# Voltmetr_MEZ.net
KiCad netlist of a schematic drawn in Altium Designer
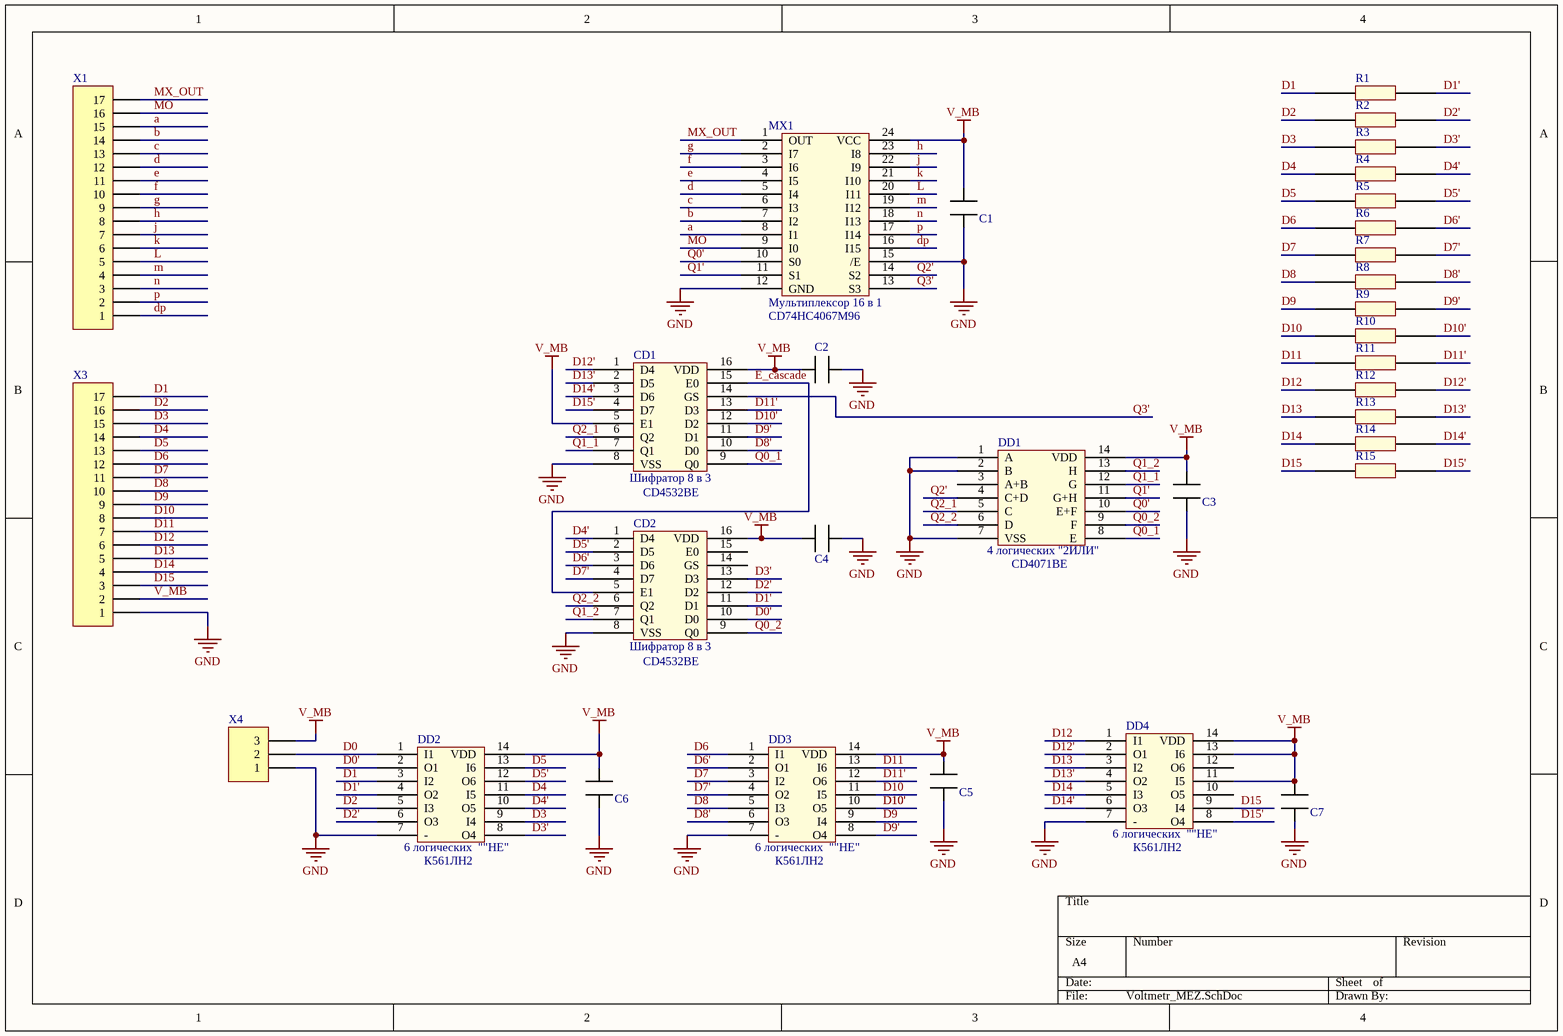
[diagram p0: Voltmetr_MEZ.SchDoc]

(export (version "E")
  (design (tool "Eeschema 10.0.6"))
  (components
    (comp (ref "C1")
      (value "CAP_SMALL")
      (footprint "CAP_SMALL")
      (libsource (lib "vpl_Schlib") (part "CAP_SMALL"))
    )
    (comp (ref "C2")
      (value "CAP_SMALL")
      (footprint "CAP_SMALL")
      (libsource (lib "vpl_Schlib") (part "CAP_SMALL"))
    )
    (comp (ref "C3")
      (value "CAP_SMALL")
      (footprint "CAP_SMALL")
      (libsource (lib "vpl_Schlib") (part "CAP_SMALL"))
    )
    (comp (ref "C4")
      (value "CAP_SMALL")
      (footprint "CAP_SMALL")
      (libsource (lib "vpl_Schlib") (part "CAP_SMALL"))
    )
    (comp (ref "C5")
      (value "CAP_SMALL")
      (footprint "CAP_SMALL")
      (libsource (lib "vpl_Schlib") (part "CAP_SMALL"))
    )
    (comp (ref "C6")
      (value "CAP_SMALL")
      (footprint "CAP_SMALL")
      (libsource (lib "vpl_Schlib") (part "CAP_SMALL"))
    )
    (comp (ref "C7")
      (value "CAP_SMALL")
      (footprint "CAP_SMALL")
      (libsource (lib "vpl_Schlib") (part "CAP_SMALL"))
    )
    (comp (ref "CD1")
      (value "CD4532BE")
      (footprint "DIP16_PANNEL")
      (description "Шифратор приоритетный 8 - 3 [DIP-16]")
      (libsource (lib "msp_SchLib") (part "CD4532BE"))
    )
    (comp (ref "CD2")
      (value "CD4532BE")
      (footprint "DIP16_PANNEL")
      (description "Шифратор приоритетный 8 - 3 [DIP-16]")
      (libsource (lib "msp_SchLib") (part "CD4532BE"))
    )
    (comp (ref "DD1")
      (value "CD4071BE")
      (footprint "Dip14_pannel")
      (description "Четыре логических элемента \"2ИЛИ\", [DIP-14]")
      (libsource (lib "msp_SchLib") (part "CD4071BE"))
    )
    (comp (ref "DD2")
      (value "К561ЛН2")
      (footprint "Dip14_pannel")
      (description "Шесть логических элементов \"HЕ\" (DIP-14)")
      (libsource (lib "msp_SchLib") (part "К561ЛН2"))
    )
    (comp (ref "DD3")
      (value "К561ЛН2")
      (footprint "Dip14_pannel")
      (description "Шесть логических элементов \"HЕ\" (DIP-14)")
      (libsource (lib "msp_SchLib") (part "К561ЛН2"))
    )
    (comp (ref "DD4")
      (value "К561ЛН2")
      (footprint "Dip14_pannel")
      (description "Шесть логических элементов \"HЕ\" (DIP-14)")
      (libsource (lib "msp_SchLib") (part "К561ЛН2"))
    )
    (comp (ref "MX1")
      (value "CD74HC4067M96")
      (footprint "SOIC-24")
      (description "16-и канальный аналоговый мультиплексор/ демультиплексор, [SO-24]")
      (libsource (lib "msp_SchLib") (part "CD74HC4067M96"))
    )
    (comp (ref "R1") (value "resistor") (footprint "RES 0805") (libsource (lib "msp_SchLib") (part "RES")))
    (comp (ref "R2") (value "resistor") (footprint "RES 0805") (libsource (lib "msp_SchLib") (part "RES")))
    (comp (ref "R3") (value "resistor") (footprint "RES 0805") (libsource (lib "msp_SchLib") (part "RES")))
    (comp (ref "R4") (value "resistor") (footprint "RES 0805") (libsource (lib "msp_SchLib") (part "RES")))
    (comp (ref "R5") (value "resistor") (footprint "RES 0805") (libsource (lib "msp_SchLib") (part "RES")))
    (comp (ref "R6") (value "resistor") (footprint "RES 0805") (libsource (lib "msp_SchLib") (part "RES")))
    (comp (ref "R7") (value "resistor") (footprint "RES 0805") (libsource (lib "msp_SchLib") (part "RES")))
    (comp (ref "R8") (value "resistor") (footprint "RES 0805") (libsource (lib "msp_SchLib") (part "RES")))
    (comp (ref "R9") (value "resistor") (footprint "RES 0805") (libsource (lib "msp_SchLib") (part "RES")))
    (comp (ref "R10") (value "resistor") (footprint "RES 0805") (libsource (lib "msp_SchLib") (part "RES")))
    (comp (ref "R11") (value "resistor") (footprint "RES 0805") (libsource (lib "msp_SchLib") (part "RES")))
    (comp (ref "R12") (value "resistor") (footprint "RES 0805") (libsource (lib "msp_SchLib") (part "RES")))
    (comp (ref "R13") (value "resistor") (footprint "RES 0805") (libsource (lib "msp_SchLib") (part "RES")))
    (comp (ref "R14") (value "resistor") (footprint "RES 0805") (libsource (lib "msp_SchLib") (part "RES")))
    (comp (ref "R15") (value "resistor") (footprint "RES 0805") (libsource (lib "msp_SchLib") (part "RES")))
    (comp (ref "X1")
      (value "Header 17")
      (footprint "HDR1X17")
      (description "Header, 17-Pin")
      (fields (field (name "PUBLISHER") "Altium Limited"))
      (libsource (lib "Miscellaneous Connectors") (part "Header 17"))
    )
    (comp (ref "X3")
      (value "Header 17")
      (footprint "HDR1X17")
      (description "Header, 17-Pin")
      (fields (field (name "PUBLISHER") "Altium Limited"))
      (libsource (lib "Miscellaneous Connectors") (part "Header 17"))
    )
    (comp (ref "X4")
      (value "Header 3")
      (footprint "HDR1X3")
      (description "Header, 3-Pin")
      (fields (field (name "PUBLISHER") "Altium Limited"))
      (libsource (lib "Miscellaneous Connectors") (part "Header 3"))
    )
  )
  (nets
    (net (code "2") (name "/D0") (class "Default")
      (node (ref "DD2") (pin "1") (pinfunction "I1_1") (pintype "passive"))
      (node (ref "X4") (pin "2") (pinfunction "2_2") (pintype "passive"))
    )
    (net (code "3") (name "/D0'") (class "Default")
      (node (ref "CD2") (pin "10") (pinfunction "D0_10") (pintype "passive"))
      (node (ref "DD2") (pin "2") (pinfunction "O1_2") (pintype "passive"))
    )
    (net (code "4") (name "/D1") (class "Default")
      (node (ref "DD2") (pin "3") (pinfunction "I2_3") (pintype "passive"))
      (node (ref "R1") (pin "1") (pinfunction "1_1") (pintype "passive"))
      (node (ref "X3") (pin "17") (pinfunction "17_17") (pintype "passive"))
    )
    (net (code "5") (name "/D1'") (class "Default")
      (node (ref "CD2") (pin "11") (pinfunction "D1_11") (pintype "passive"))
      (node (ref "DD2") (pin "4") (pinfunction "O2_4") (pintype "passive"))
      (node (ref "R1") (pin "2") (pinfunction "2_2") (pintype "passive"))
    )
    (net (code "6") (name "/D2") (class "Default")
      (node (ref "DD2") (pin "5") (pinfunction "I3_5") (pintype "passive"))
      (node (ref "R2") (pin "1") (pinfunction "1_1") (pintype "passive"))
      (node (ref "X3") (pin "16") (pinfunction "16_16") (pintype "passive"))
    )
    (net (code "7") (name "/D2'") (class "Default")
      (node (ref "CD2") (pin "12") (pinfunction "D2_12") (pintype "passive"))
      (node (ref "DD2") (pin "6") (pinfunction "O3_6") (pintype "passive"))
      (node (ref "R2") (pin "2") (pinfunction "2_2") (pintype "passive"))
    )
    (net (code "8") (name "/D3") (class "Default")
      (node (ref "DD2") (pin "9") (pinfunction "I4_9") (pintype "passive"))
      (node (ref "R3") (pin "1") (pinfunction "1_1") (pintype "passive"))
      (node (ref "X3") (pin "15") (pinfunction "15_15") (pintype "passive"))
    )
    (net (code "9") (name "/D3'") (class "Default")
      (node (ref "CD2") (pin "13") (pinfunction "D3_13") (pintype "passive"))
      (node (ref "DD2") (pin "8") (pinfunction "O4_8") (pintype "passive"))
      (node (ref "R3") (pin "2") (pinfunction "2_2") (pintype "passive"))
    )
    (net (code "10") (name "/D4") (class "Default")
      (node (ref "DD2") (pin "11") (pinfunction "I5_11") (pintype "passive"))
      (node (ref "R4") (pin "1") (pinfunction "1_1") (pintype "passive"))
      (node (ref "X3") (pin "14") (pinfunction "14_14") (pintype "passive"))
    )
    (net (code "11") (name "/D4'") (class "Default")
      (node (ref "CD2") (pin "1") (pinfunction "D4_1") (pintype "passive"))
      (node (ref "DD2") (pin "10") (pinfunction "O5_10") (pintype "passive"))
      (node (ref "R4") (pin "2") (pinfunction "2_2") (pintype "passive"))
    )
    (net (code "12") (name "/D5") (class "Default")
      (node (ref "DD2") (pin "13") (pinfunction "I6_13") (pintype "passive"))
      (node (ref "R5") (pin "1") (pinfunction "1_1") (pintype "passive"))
      (node (ref "X3") (pin "13") (pinfunction "13_13") (pintype "passive"))
    )
    (net (code "13") (name "/D5'") (class "Default")
      (node (ref "CD2") (pin "2") (pinfunction "D5_2") (pintype "passive"))
      (node (ref "DD2") (pin "12") (pinfunction "O6_12") (pintype "passive"))
      (node (ref "R5") (pin "2") (pinfunction "2_2") (pintype "passive"))
    )
    (net (code "14") (name "/D6") (class "Default")
      (node (ref "DD3") (pin "1") (pinfunction "I1_1") (pintype "passive"))
      (node (ref "R6") (pin "1") (pinfunction "1_1") (pintype "passive"))
      (node (ref "X3") (pin "12") (pinfunction "12_12") (pintype "passive"))
    )
    (net (code "15") (name "/D6'") (class "Default")
      (node (ref "CD2") (pin "3") (pinfunction "D6_3") (pintype "passive"))
      (node (ref "DD3") (pin "2") (pinfunction "O1_2") (pintype "passive"))
      (node (ref "R6") (pin "2") (pinfunction "2_2") (pintype "passive"))
    )
    (net (code "16") (name "/D7") (class "Default")
      (node (ref "DD3") (pin "3") (pinfunction "I2_3") (pintype "passive"))
      (node (ref "R7") (pin "1") (pinfunction "1_1") (pintype "passive"))
      (node (ref "X3") (pin "11") (pinfunction "11_11") (pintype "passive"))
    )
    (net (code "17") (name "/D7'") (class "Default")
      (node (ref "CD2") (pin "4") (pinfunction "D7_4") (pintype "passive"))
      (node (ref "DD3") (pin "4") (pinfunction "O2_4") (pintype "passive"))
      (node (ref "R7") (pin "2") (pinfunction "2_2") (pintype "passive"))
    )
    (net (code "18") (name "/D8") (class "Default")
      (node (ref "DD3") (pin "5") (pinfunction "I3_5") (pintype "passive"))
      (node (ref "R8") (pin "1") (pinfunction "1_1") (pintype "passive"))
      (node (ref "X3") (pin "10") (pinfunction "10_10") (pintype "passive"))
    )
    (net (code "19") (name "/D8'") (class "Default")
      (node (ref "CD1") (pin "10") (pinfunction "D0_10") (pintype "passive"))
      (node (ref "DD3") (pin "6") (pinfunction "O3_6") (pintype "passive"))
      (node (ref "R8") (pin "2") (pinfunction "2_2") (pintype "passive"))
    )
    (net (code "20") (name "/D9") (class "Default")
      (node (ref "DD3") (pin "9") (pinfunction "I4_9") (pintype "passive"))
      (node (ref "R9") (pin "1") (pinfunction "1_1") (pintype "passive"))
      (node (ref "X3") (pin "9") (pinfunction "9_9") (pintype "passive"))
    )
    (net (code "21") (name "/D9'") (class "Default")
      (node (ref "CD1") (pin "11") (pinfunction "D1_11") (pintype "passive"))
      (node (ref "DD3") (pin "8") (pinfunction "O4_8") (pintype "passive"))
      (node (ref "R9") (pin "2") (pinfunction "2_2") (pintype "passive"))
    )
    (net (code "22") (name "/D10") (class "Default")
      (node (ref "DD3") (pin "11") (pinfunction "I5_11") (pintype "passive"))
      (node (ref "R10") (pin "1") (pinfunction "1_1") (pintype "passive"))
      (node (ref "X3") (pin "8") (pinfunction "8_8") (pintype "passive"))
    )
    (net (code "23") (name "/D10'") (class "Default")
      (node (ref "CD1") (pin "12") (pinfunction "D2_12") (pintype "passive"))
      (node (ref "DD3") (pin "10") (pinfunction "O5_10") (pintype "passive"))
      (node (ref "R10") (pin "2") (pinfunction "2_2") (pintype "passive"))
    )
    (net (code "24") (name "/D11") (class "Default")
      (node (ref "DD3") (pin "13") (pinfunction "I6_13") (pintype "passive"))
      (node (ref "R11") (pin "1") (pinfunction "1_1") (pintype "passive"))
      (node (ref "X3") (pin "7") (pinfunction "7_7") (pintype "passive"))
    )
    (net (code "25") (name "/D11'") (class "Default")
      (node (ref "CD1") (pin "13") (pinfunction "D3_13") (pintype "passive"))
      (node (ref "DD3") (pin "12") (pinfunction "O6_12") (pintype "passive"))
      (node (ref "R11") (pin "2") (pinfunction "2_2") (pintype "passive"))
    )
    (net (code "26") (name "/D12") (class "Default")
      (node (ref "DD4") (pin "1") (pinfunction "I1_1") (pintype "passive"))
      (node (ref "R12") (pin "1") (pinfunction "1_1") (pintype "passive"))
      (node (ref "X3") (pin "6") (pinfunction "6_6") (pintype "passive"))
    )
    (net (code "27") (name "/D12'") (class "Default")
      (node (ref "CD1") (pin "1") (pinfunction "D4_1") (pintype "passive"))
      (node (ref "DD4") (pin "2") (pinfunction "O1_2") (pintype "passive"))
      (node (ref "R12") (pin "2") (pinfunction "2_2") (pintype "passive"))
    )
    (net (code "28") (name "/D13") (class "Default")
      (node (ref "DD4") (pin "3") (pinfunction "I2_3") (pintype "passive"))
      (node (ref "R13") (pin "1") (pinfunction "1_1") (pintype "passive"))
      (node (ref "X3") (pin "5") (pinfunction "5_5") (pintype "passive"))
    )
    (net (code "29") (name "/D13'") (class "Default")
      (node (ref "CD1") (pin "2") (pinfunction "D5_2") (pintype "passive"))
      (node (ref "DD4") (pin "4") (pinfunction "O2_4") (pintype "passive"))
      (node (ref "R13") (pin "2") (pinfunction "2_2") (pintype "passive"))
    )
    (net (code "30") (name "/D14") (class "Default")
      (node (ref "DD4") (pin "5") (pinfunction "I3_5") (pintype "passive"))
      (node (ref "R14") (pin "1") (pinfunction "1_1") (pintype "passive"))
      (node (ref "X3") (pin "4") (pinfunction "4_4") (pintype "passive"))
    )
    (net (code "31") (name "/D14'") (class "Default")
      (node (ref "CD1") (pin "3") (pinfunction "D6_3") (pintype "passive"))
      (node (ref "DD4") (pin "6") (pinfunction "O3_6") (pintype "passive"))
      (node (ref "R14") (pin "2") (pinfunction "2_2") (pintype "passive"))
    )
    (net (code "32") (name "/D15") (class "Default")
      (node (ref "DD4") (pin "9") (pinfunction "I4_9") (pintype "passive"))
      (node (ref "R15") (pin "1") (pinfunction "1_1") (pintype "passive"))
      (node (ref "X3") (pin "3") (pinfunction "3_3") (pintype "passive"))
    )
    (net (code "33") (name "/D15'") (class "Default")
      (node (ref "CD1") (pin "4") (pinfunction "D7_4") (pintype "passive"))
      (node (ref "DD4") (pin "8") (pinfunction "O4_8") (pintype "passive"))
      (node (ref "R15") (pin "2") (pinfunction "2_2") (pintype "passive"))
    )
    (net (code "34") (name "/E_cascade") (class "Default")
      (node (ref "CD1") (pin "15") (pinfunction "E0_15") (pintype "passive"))
      (node (ref "CD2") (pin "5") (pinfunction "E1_5") (pintype "passive"))
    )
    (net (code "35") (name "/L") (class "Default")
      (node (ref "MX1") (pin "20") (pinfunction "I11_20") (pintype "passive"))
      (node (ref "X1") (pin "5") (pinfunction "5_5") (pintype "passive"))
    )
    (net (code "36") (name "/MX_OUT") (class "Default")
      (node (ref "MX1") (pin "1") (pinfunction "OUT_1") (pintype "passive"))
      (node (ref "X1") (pin "17") (pinfunction "17_17") (pintype "passive"))
    )
    (net (code "37") (name "/Q0'") (class "Default")
      (node (ref "DD1") (pin "10") (pinfunction "E+F_10") (pintype "passive"))
      (node (ref "MX1") (pin "10") (pinfunction "S0_10") (pintype "passive"))
    )
    (net (code "38") (name "/Q0_1") (class "Default")
      (node (ref "CD1") (pin "9") (pinfunction "Q0_9") (pintype "passive"))
      (node (ref "DD1") (pin "8") (pinfunction "E_8") (pintype "passive"))
    )
    (net (code "39") (name "/Q0_2") (class "Default")
      (node (ref "CD2") (pin "9") (pinfunction "Q0_9") (pintype "passive"))
      (node (ref "DD1") (pin "9") (pinfunction "F_9") (pintype "passive"))
    )
    (net (code "40") (name "/Q1'") (class "Default")
      (node (ref "DD1") (pin "11") (pinfunction "G+H_11") (pintype "passive"))
      (node (ref "MX1") (pin "11") (pinfunction "S1_11") (pintype "passive"))
    )
    (net (code "41") (name "/Q1_1") (class "Default")
      (node (ref "CD1") (pin "7") (pinfunction "Q1_7") (pintype "passive"))
      (node (ref "DD1") (pin "12") (pinfunction "G_12") (pintype "passive"))
    )
    (net (code "42") (name "/Q1_2") (class "Default")
      (node (ref "CD2") (pin "7") (pinfunction "Q1_7") (pintype "passive"))
      (node (ref "DD1") (pin "13") (pinfunction "H_13") (pintype "passive"))
    )
    (net (code "43") (name "/Q2'") (class "Default")
      (node (ref "DD1") (pin "4") (pinfunction "C+D_4") (pintype "passive"))
      (node (ref "MX1") (pin "14") (pinfunction "S2_14") (pintype "passive"))
    )
    (net (code "44") (name "/Q2_1") (class "Default")
      (node (ref "CD1") (pin "6") (pinfunction "Q2_6") (pintype "passive"))
      (node (ref "DD1") (pin "5") (pinfunction "C_5") (pintype "passive"))
    )
    (net (code "45") (name "/Q2_2") (class "Default")
      (node (ref "CD2") (pin "6") (pinfunction "Q2_6") (pintype "passive"))
      (node (ref "DD1") (pin "6") (pinfunction "D_6") (pintype "passive"))
    )
    (net (code "46") (name "/Q3'") (class "Default")
      (node (ref "CD1") (pin "14") (pinfunction "GS_14") (pintype "passive"))
      (node (ref "MX1") (pin "13") (pinfunction "S3_13") (pintype "passive"))
    )
    (net (code "47") (name "/a") (class "Default")
      (node (ref "MX1") (pin "8") (pinfunction "I1_8") (pintype "passive"))
      (node (ref "X1") (pin "15") (pinfunction "15_15") (pintype "passive"))
    )
    (net (code "48") (name "/b") (class "Default")
      (node (ref "MX1") (pin "7") (pinfunction "I2_7") (pintype "passive"))
      (node (ref "X1") (pin "14") (pinfunction "14_14") (pintype "passive"))
    )
    (net (code "49") (name "/c") (class "Default")
      (node (ref "MX1") (pin "6") (pinfunction "I3_6") (pintype "passive"))
      (node (ref "X1") (pin "13") (pinfunction "13_13") (pintype "passive"))
    )
    (net (code "50") (name "/d") (class "Default")
      (node (ref "MX1") (pin "5") (pinfunction "I4_5") (pintype "passive"))
      (node (ref "X1") (pin "12") (pinfunction "12_12") (pintype "passive"))
    )
    (net (code "51") (name "/dp") (class "Default")
      (node (ref "MX1") (pin "16") (pinfunction "I15_16") (pintype "passive"))
      (node (ref "X1") (pin "1") (pinfunction "1_1") (pintype "passive"))
    )
    (net (code "52") (name "/e") (class "Default")
      (node (ref "MX1") (pin "4") (pinfunction "I5_4") (pintype "passive"))
      (node (ref "X1") (pin "11") (pinfunction "11_11") (pintype "passive"))
    )
    (net (code "53") (name "/f") (class "Default")
      (node (ref "MX1") (pin "3") (pinfunction "I6_3") (pintype "passive"))
      (node (ref "X1") (pin "10") (pinfunction "10_10") (pintype "passive"))
    )
    (net (code "54") (name "/g") (class "Default")
      (node (ref "MX1") (pin "2") (pinfunction "I7_2") (pintype "passive"))
      (node (ref "X1") (pin "9") (pinfunction "9_9") (pintype "passive"))
    )
    (net (code "55") (name "/h") (class "Default")
      (node (ref "MX1") (pin "23") (pinfunction "I8_23") (pintype "passive"))
      (node (ref "X1") (pin "8") (pinfunction "8_8") (pintype "passive"))
    )
    (net (code "56") (name "/j") (class "Default")
      (node (ref "MX1") (pin "22") (pinfunction "I9_22") (pintype "passive"))
      (node (ref "X1") (pin "7") (pinfunction "7_7") (pintype "passive"))
    )
    (net (code "57") (name "/k") (class "Default")
      (node (ref "MX1") (pin "21") (pinfunction "I10_21") (pintype "passive"))
      (node (ref "X1") (pin "6") (pinfunction "6_6") (pintype "passive"))
    )
    (net (code "58") (name "/m") (class "Default")
      (node (ref "MX1") (pin "19") (pinfunction "I12_19") (pintype "passive"))
      (node (ref "X1") (pin "4") (pinfunction "4_4") (pintype "passive"))
    )
    (net (code "59") (name "/n") (class "Default")
      (node (ref "MX1") (pin "18") (pinfunction "I13_18") (pintype "passive"))
      (node (ref "X1") (pin "3") (pinfunction "3_3") (pintype "passive"))
    )
    (net (code "60") (name "/p") (class "Default")
      (node (ref "MX1") (pin "17") (pinfunction "I14_17") (pintype "passive"))
      (node (ref "X1") (pin "2") (pinfunction "2_2") (pintype "passive"))
    )
    (net (code "61") (name "/~{MO}") (class "Default")
      (node (ref "MX1") (pin "9") (pinfunction "I0_9") (pintype "passive"))
      (node (ref "X1") (pin "16") (pinfunction "16_16") (pintype "passive"))
    )
    (net (code "62") (name "GND") (class "Default")
      (node (ref "C1") (pin "1") (pinfunction "1_1") (pintype "passive"))
      (node (ref "C2") (pin "2") (pinfunction "2_2") (pintype "passive"))
      (node (ref "C3") (pin "1") (pinfunction "1_1") (pintype "passive"))
      (node (ref "C4") (pin "1") (pinfunction "1_1") (pintype "passive"))
      (node (ref "C5") (pin "1") (pinfunction "1_1") (pintype "passive"))
      (node (ref "C6") (pin "1") (pinfunction "1_1") (pintype "passive"))
      (node (ref "C7") (pin "1") (pinfunction "1_1") (pintype "passive"))
      (node (ref "CD1") (pin "8") (pinfunction "VSS_8") (pintype "passive"))
      (node (ref "CD2") (pin "8") (pinfunction "VSS_8") (pintype "passive"))
      (node (ref "DD1") (pin "1") (pinfunction "A_1") (pintype "passive"))
      (node (ref "DD1") (pin "2") (pinfunction "B_2") (pintype "passive"))
      (node (ref "DD1") (pin "7") (pinfunction "VSS_7") (pintype "passive"))
      (node (ref "DD2") (pin "7") (pinfunction "-_7") (pintype "passive"))
      (node (ref "DD3") (pin "7") (pinfunction "-_7") (pintype "passive"))
      (node (ref "DD4") (pin "7") (pinfunction "-_7") (pintype "passive"))
      (node (ref "MX1") (pin "12") (pinfunction "GND_12") (pintype "passive"))
      (node (ref "MX1") (pin "15") (pinfunction "/E_15") (pintype "passive"))
      (node (ref "X3") (pin "1") (pinfunction "1_1") (pintype "passive"))
      (node (ref "X4") (pin "1") (pinfunction "1_1") (pintype "passive"))
    )
    (net (code "63") (name "V_MB") (class "Default")
      (node (ref "C1") (pin "2") (pinfunction "2_2") (pintype "passive"))
      (node (ref "C2") (pin "1") (pinfunction "1_1") (pintype "passive"))
      (node (ref "C3") (pin "2") (pinfunction "2_2") (pintype "passive"))
      (node (ref "C4") (pin "2") (pinfunction "2_2") (pintype "passive"))
      (node (ref "C5") (pin "2") (pinfunction "2_2") (pintype "passive"))
      (node (ref "C6") (pin "2") (pinfunction "2_2") (pintype "passive"))
      (node (ref "C7") (pin "2") (pinfunction "2_2") (pintype "passive"))
      (node (ref "CD1") (pin "16") (pinfunction "VDD_16") (pintype "passive"))
      (node (ref "CD1") (pin "5") (pinfunction "E1_5") (pintype "passive"))
      (node (ref "CD2") (pin "16") (pinfunction "VDD_16") (pintype "passive"))
      (node (ref "DD1") (pin "14") (pinfunction "VDD_14") (pintype "passive"))
      (node (ref "DD2") (pin "14") (pinfunction "VDD_14") (pintype "passive"))
      (node (ref "DD3") (pin "14") (pinfunction "VDD_14") (pintype "passive"))
      (node (ref "DD4") (pin "11") (pinfunction "I5_11") (pintype "passive"))
      (node (ref "DD4") (pin "13") (pinfunction "I6_13") (pintype "passive"))
      (node (ref "DD4") (pin "14") (pinfunction "VDD_14") (pintype "passive"))
      (node (ref "MX1") (pin "24") (pinfunction "VCC_24") (pintype "passive"))
      (node (ref "X3") (pin "2") (pinfunction "2_2") (pintype "passive"))
      (node (ref "X4") (pin "3") (pinfunction "3_3") (pintype "passive"))
    )
    (net (code "64") (name "unconnected-(CD2-E0-Pad15)") (class "Default")
      (node (ref "CD2") (pin "15") (pinfunction "E0_15") (pintype "passive"))
    )
    (net (code "65") (name "unconnected-(CD2-GS-Pad14)") (class "Default")
      (node (ref "CD2") (pin "14") (pinfunction "GS_14") (pintype "passive"))
    )
    (net (code "66") (name "unconnected-(DD1-A+B-Pad3)") (class "Default")
      (node (ref "DD1") (pin "3") (pinfunction "A+B_3") (pintype "passive"))
    )
    (net (code "67") (name "unconnected-(DD4-O5-Pad10)") (class "Default")
      (node (ref "DD4") (pin "10") (pinfunction "O5_10") (pintype "passive"))
    )
    (net (code "68") (name "unconnected-(DD4-O6-Pad12)") (class "Default")
      (node (ref "DD4") (pin "12") (pinfunction "O6_12") (pintype "passive"))
    )
  )
)
